# 01_-_Main.net
KiCad netlist of a schematic drawn in Altium Designer
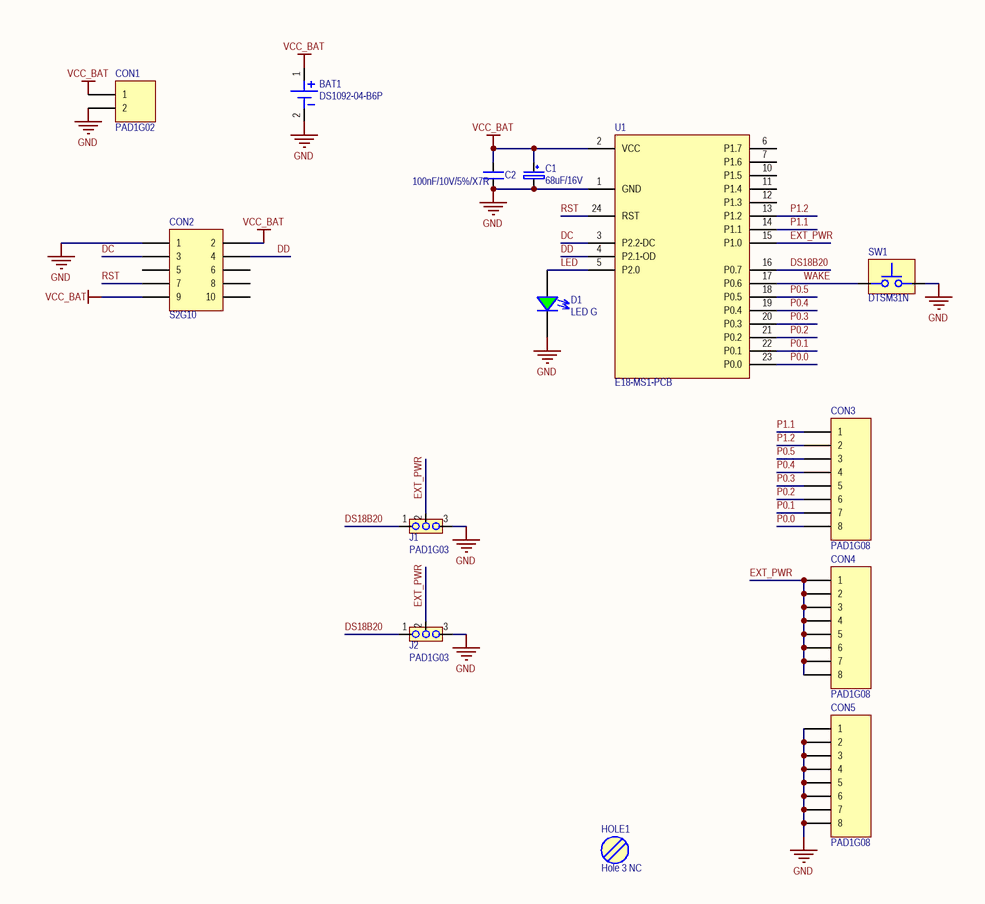
[diagram p0: 01 - Main.SchDoc]

(export (version "E")
  (design (tool "Eeschema 10.0.6"))
  (components
    (comp (ref "BAT1")
      (value "DS1092-04-B6P")
      (footprint "DS1092-04-B6P")
      (libsource (lib "Battery") (part "DS1092-04-B6P"))
    )
    (comp (ref "C1")
      (value "68uF/16V")
      (footprint "C-SMDD")
      (description "SMD Tantalum Capacitor SMDD 68uF/16V")
      (fields (field (name "VOLTAGE") "16V"))
      (libsource (lib "Y Soft Corporation, a.s") (part "CapacitorPOL"))
    )
    (comp (ref "C2")
      (value "100nF/10V/5%/X7R")
      (footprint "C-0603")
      (description "SMD Ceramic Capacitor 0603 100nF/10V/5%/X7R")
      (fields (field (name "VOLTAGE") "10V") (field (name "TOLERANCE") "5%"))
      (libsource (lib "Y Soft Corporation, a.s") (part "CapacitorNP"))
    )
    (comp (ref "CON1")
      (value "PAD1G02")
      (footprint "HDR1X02S")
      (description "1x2pin single row pads, 2.54mm")
      (libsource (lib "Y Soft Corporation, a.s") (part "Header 2"))
    )
    (comp (ref "CON2")
      (value "S2G10")
      (footprint "HDR2X10")
      (description "2x5pin dual row header, 2.54mm")
      (libsource (lib "Y Soft Corporation, a.s") (part "Header 5X2"))
    )
    (comp (ref "CON3")
      (value "PAD1G08")
      (footprint "HDR1X08S")
      (description "1x8pin single row pads, 2.54mm")
      (libsource (lib "Y Soft Corporation, a.s") (part "Header 8"))
    )
    (comp (ref "CON4")
      (value "PAD1G08")
      (footprint "HDR1X08S")
      (description "1x8pin single row pads, 2.54mm")
      (libsource (lib "Y Soft Corporation, a.s") (part "Header 8"))
    )
    (comp (ref "CON5")
      (value "PAD1G08")
      (footprint "HDR1X08S")
      (description "1x8pin single row pads, 2.54mm")
      (libsource (lib "Y Soft Corporation, a.s") (part "Header 8"))
    )
    (comp (ref "D1")
      (value "LED G")
      (footprint "LED-0603 GREEN")
      (description "LED; SMD; 0603; zelená; 4-15mcd; 1,6x0,8x1,1mm; 120°; 2,2÷2,5V; 20mA")
      (libsource (lib "Y Soft Corporation, a.s") (part "LED-G"))
    )
    (comp (ref "HOLE1")
      (value "Hole 3 NC")
      (footprint "Hole 3 NC")
      (description "Hole 3mm Unconnected")
      (libsource (lib "Y Soft Corporation, a.s") (part "Hole Unconnected"))
    )
    (comp (ref "J1")
      (value "PAD1G03")
      (footprint "HDR1X03S")
      (description "3 pin jumper")
      (libsource (lib "Y Soft Corporation, a.s") (part "Jumper 03"))
    )
    (comp (ref "J2")
      (value "PAD1G03")
      (footprint "HDR1X03S")
      (description "3 pin jumper")
      (libsource (lib "Y Soft Corporation, a.s") (part "Jumper 03"))
    )
    (comp (ref "SW1")
      (value "DTSM31N")
      (footprint "DTSM31N")
      (description "SMT tactile switch, 2 pin")
      (libsource (lib "Y Soft Corporation, a.s") (part "Button 2P"))
    )
    (comp (ref "U1")
      (value "E18-MS1-PCB")
      (footprint "MS1-E18-PCB")
      (libsource (lib "eByte") (part "E18-MS1-PCB"))
    )
  )
  (nets
    (net (code "1") (name "/DC") (class "Default")
      (node (ref "CON2") (pin "3") (pinfunction "3_3") (pintype "passive"))
      (node (ref "U1") (pin "3") (pinfunction "P2.2-DC_3") (pintype "passive"))
    )
    (net (code "2") (name "/DD") (class "Default")
      (node (ref "CON2") (pin "4") (pinfunction "4_4") (pintype "passive"))
      (node (ref "U1") (pin "4") (pinfunction "P2.1-OD_4") (pintype "passive"))
    )
    (net (code "3") (name "/DS18B20") (class "Default")
      (node (ref "J1") (pin "1") (pinfunction "1_1") (pintype "passive"))
      (node (ref "J2") (pin "1") (pinfunction "1_1") (pintype "passive"))
      (node (ref "U1") (pin "16") (pinfunction "P0.7_16") (pintype "passive"))
    )
    (net (code "4") (name "/EXT_PWR") (class "Default")
      (node (ref "CON4") (pin "1") (pinfunction "1_1") (pintype "passive"))
      (node (ref "CON4") (pin "2") (pinfunction "2_2") (pintype "passive"))
      (node (ref "CON4") (pin "3") (pinfunction "3_3") (pintype "passive"))
      (node (ref "CON4") (pin "4") (pinfunction "4_4") (pintype "passive"))
      (node (ref "CON4") (pin "5") (pinfunction "5_5") (pintype "passive"))
      (node (ref "CON4") (pin "6") (pinfunction "6_6") (pintype "passive"))
      (node (ref "CON4") (pin "7") (pinfunction "7_7") (pintype "passive"))
      (node (ref "CON4") (pin "8") (pinfunction "8_8") (pintype "passive"))
      (node (ref "J1") (pin "2") (pinfunction "2_2") (pintype "passive"))
      (node (ref "J2") (pin "2") (pinfunction "2_2") (pintype "passive"))
      (node (ref "U1") (pin "15") (pinfunction "P1.0_15") (pintype "passive"))
    )
    (net (code "5") (name "/LED") (class "Default")
      (node (ref "D1") (pin "2") (pinfunction "A_2") (pintype "passive"))
      (node (ref "U1") (pin "5") (pinfunction "P2.0_5") (pintype "passive"))
    )
    (net (code "6") (name "/P0.0") (class "Default")
      (node (ref "CON3") (pin "8") (pinfunction "8_8") (pintype "passive"))
      (node (ref "U1") (pin "23") (pinfunction "P0.0_23") (pintype "passive"))
    )
    (net (code "7") (name "/P0.1") (class "Default")
      (node (ref "CON3") (pin "7") (pinfunction "7_7") (pintype "passive"))
      (node (ref "U1") (pin "22") (pinfunction "P0.1_22") (pintype "passive"))
    )
    (net (code "8") (name "/P0.2") (class "Default")
      (node (ref "CON3") (pin "6") (pinfunction "6_6") (pintype "passive"))
      (node (ref "U1") (pin "21") (pinfunction "P0.2_21") (pintype "passive"))
    )
    (net (code "9") (name "/P0.3") (class "Default")
      (node (ref "CON3") (pin "5") (pinfunction "5_5") (pintype "passive"))
      (node (ref "U1") (pin "20") (pinfunction "P0.3_20") (pintype "passive"))
    )
    (net (code "10") (name "/P0.4") (class "Default")
      (node (ref "CON3") (pin "4") (pinfunction "4_4") (pintype "passive"))
      (node (ref "U1") (pin "19") (pinfunction "P0.4_19") (pintype "passive"))
    )
    (net (code "11") (name "/P0.5") (class "Default")
      (node (ref "CON3") (pin "3") (pinfunction "3_3") (pintype "passive"))
      (node (ref "U1") (pin "18") (pinfunction "P0.5_18") (pintype "passive"))
    )
    (net (code "12") (name "/P1.1") (class "Default")
      (node (ref "CON3") (pin "1") (pinfunction "1_1") (pintype "passive"))
      (node (ref "U1") (pin "14") (pinfunction "P1.1_14") (pintype "passive"))
    )
    (net (code "13") (name "/P1.2") (class "Default")
      (node (ref "CON3") (pin "2") (pinfunction "2_2") (pintype "passive"))
      (node (ref "U1") (pin "13") (pinfunction "P1.2_13") (pintype "passive"))
    )
    (net (code "14") (name "/RST") (class "Default")
      (node (ref "CON2") (pin "7") (pinfunction "7_7") (pintype "passive"))
      (node (ref "U1") (pin "24") (pinfunction "RST_24") (pintype "passive"))
    )
    (net (code "15") (name "/WAKE") (class "Default")
      (node (ref "SW1") (pin "1") (pinfunction "1_1") (pintype "passive"))
      (node (ref "U1") (pin "17") (pinfunction "P0.6_17") (pintype "passive"))
    )
    (net (code "16") (name "GND") (class "Default")
      (node (ref "BAT1") (pin "2") (pinfunction "-_2") (pintype "passive"))
      (node (ref "C1") (pin "2") (pinfunction "2_2") (pintype "passive"))
      (node (ref "C2") (pin "1") (pinfunction "1_1") (pintype "passive"))
      (node (ref "CON1") (pin "2") (pinfunction "2_2") (pintype "passive"))
      (node (ref "CON2") (pin "1") (pinfunction "1_1") (pintype "passive"))
      (node (ref "CON5") (pin "1") (pinfunction "1_1") (pintype "passive"))
      (node (ref "CON5") (pin "2") (pinfunction "2_2") (pintype "passive"))
      (node (ref "CON5") (pin "3") (pinfunction "3_3") (pintype "passive"))
      (node (ref "CON5") (pin "4") (pinfunction "4_4") (pintype "passive"))
      (node (ref "CON5") (pin "5") (pinfunction "5_5") (pintype "passive"))
      (node (ref "CON5") (pin "6") (pinfunction "6_6") (pintype "passive"))
      (node (ref "CON5") (pin "7") (pinfunction "7_7") (pintype "passive"))
      (node (ref "CON5") (pin "8") (pinfunction "8_8") (pintype "passive"))
      (node (ref "D1") (pin "1") (pinfunction "K_1") (pintype "passive"))
      (node (ref "J1") (pin "3") (pinfunction "3_3") (pintype "passive"))
      (node (ref "J2") (pin "3") (pinfunction "3_3") (pintype "passive"))
      (node (ref "SW1") (pin "2") (pinfunction "2_2") (pintype "passive"))
      (node (ref "U1") (pin "1") (pinfunction "GND_1") (pintype "power_in"))
    )
    (net (code "17") (name "VCC_BAT") (class "Default")
      (node (ref "BAT1") (pin "1") (pinfunction "+_1") (pintype "passive"))
      (node (ref "C1") (pin "1") (pinfunction "1_1") (pintype "passive"))
      (node (ref "C2") (pin "2") (pinfunction "2_2") (pintype "passive"))
      (node (ref "CON1") (pin "1") (pinfunction "1_1") (pintype "passive"))
      (node (ref "CON2") (pin "2") (pinfunction "2_2") (pintype "passive"))
      (node (ref "CON2") (pin "9") (pinfunction "9_9") (pintype "passive"))
      (node (ref "U1") (pin "2") (pinfunction "VCC_2") (pintype "power_in"))
    )
    (net (code "18") (name "unconnected-(CON2-Pad5)") (class "Default")
      (node (ref "CON2") (pin "5") (pinfunction "5_5") (pintype "passive"))
    )
    (net (code "19") (name "unconnected-(CON2-Pad6)") (class "Default")
      (node (ref "CON2") (pin "6") (pinfunction "6_6") (pintype "passive"))
    )
    (net (code "20") (name "unconnected-(CON2-Pad8)") (class "Default")
      (node (ref "CON2") (pin "8") (pinfunction "8_8") (pintype "passive"))
    )
    (net (code "21") (name "unconnected-(CON2-Pad10)") (class "Default")
      (node (ref "CON2") (pin "10") (pinfunction "10_10") (pintype "passive"))
    )
    (net (code "22") (name "unconnected-(U1-P1.3-Pad12)") (class "Default")
      (node (ref "U1") (pin "12") (pinfunction "P1.3_12") (pintype "passive"))
    )
    (net (code "23") (name "unconnected-(U1-P1.4-Pad11)") (class "Default")
      (node (ref "U1") (pin "11") (pinfunction "P1.4_11") (pintype "passive"))
    )
    (net (code "24") (name "unconnected-(U1-P1.5-Pad10)") (class "Default")
      (node (ref "U1") (pin "10") (pinfunction "P1.5_10") (pintype "passive"))
    )
    (net (code "25") (name "unconnected-(U1-P1.6-Pad7)") (class "Default")
      (node (ref "U1") (pin "7") (pinfunction "P1.6_7") (pintype "passive"))
    )
    (net (code "26") (name "unconnected-(U1-P1.7-Pad6)") (class "Default")
      (node (ref "U1") (pin "6") (pinfunction "P1.7_6") (pintype "passive"))
    )
  )
)
